# PowerPrototype.net
KiCad netlist of a schematic drawn in EAGLE
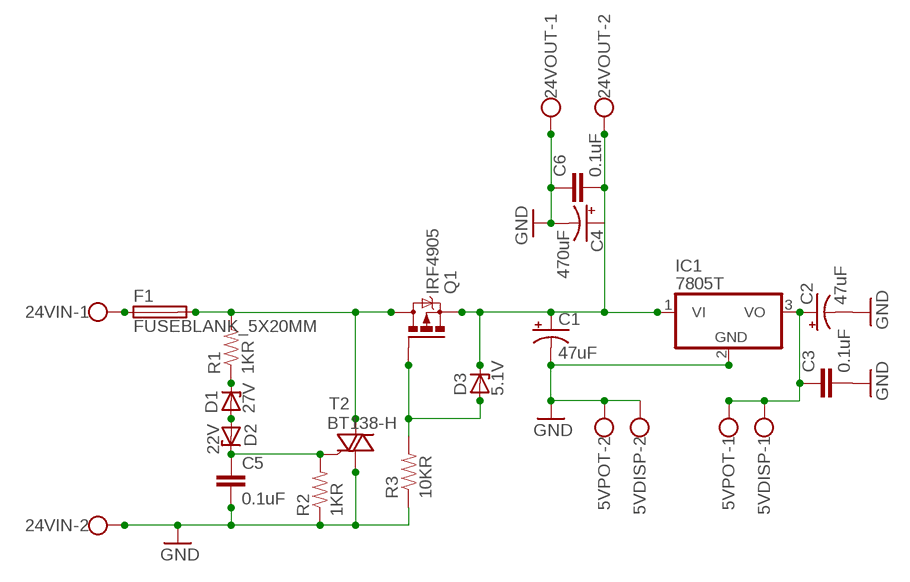
[diagram p0: schematic, sheet 1]

(export (version "E")
  (design (tool "Eeschema 10.0.6"))
  (components
    (comp (ref "5VDISP")
      (value "W237-102")
      (footprint "eagle-import:W237-102")
      (fields (field (name "MPN") "237-102"))
      (libsource (lib "eagle-import") (part "W237-102"))
    )
    (comp (ref "5VPOT")
      (value "W237-102")
      (footprint "eagle-import:W237-102")
      (fields (field (name "MPN") "237-102"))
      (libsource (lib "eagle-import") (part "W237-102"))
    )
    (comp (ref "24VIN")
      (value "W237-102")
      (footprint "eagle-import:W237-102")
      (fields (field (name "MPN") "237-102"))
      (libsource (lib "eagle-import") (part "W237-102"))
    )
    (comp (ref "24VOUT")
      (value "W237-102")
      (footprint "eagle-import:W237-102")
      (fields (field (name "MPN") "237-102"))
      (libsource (lib "eagle-import") (part "W237-102"))
    )
    (comp (ref "C1")
      (value "47uF")
      (footprint "eagle-import:E2,5-5")
      (libsource (lib "eagle-import") (part "CPOL-USE2.5-5"))
    )
    (comp (ref "C2")
      (value "47uF")
      (footprint "eagle-import:E2,5-5")
      (libsource (lib "eagle-import") (part "CPOL-USE2.5-5"))
    )
    (comp (ref "C3")
      (value "0.1uF")
      (footprint "eagle-import:CAP-PTH-5MM")
      (libsource (lib "eagle-import") (part "CAPPTH1"))
    )
    (comp (ref "C4")
      (value "470uF")
      (footprint "eagle-import:E2,5-5")
      (libsource (lib "eagle-import") (part "CPOL-USE2.5-5"))
    )
    (comp (ref "C5")
      (value "0.1uF")
      (footprint "eagle-import:CAP-PTH-5MM")
      (libsource (lib "eagle-import") (part "CAPPTH1"))
    )
    (comp (ref "C6")
      (value "0.1uF")
      (footprint "eagle-import:CAP-PTH-5MM")
      (libsource (lib "eagle-import") (part "CAPPTH1"))
    )
    (comp (ref "D1")
      (value "27V")
      (footprint "eagle-import:ZDIO-5")
      (libsource (lib "eagle-import") (part "ZENER-DIODEZD-5"))
    )
    (comp (ref "D2")
      (value "22V")
      (footprint "eagle-import:ZDIO-5")
      (libsource (lib "eagle-import") (part "ZENER-DIODEZD-5"))
    )
    (comp (ref "D3")
      (value "5.1V")
      (footprint "eagle-import:ZDIO-7.5")
      (libsource (lib "eagle-import") (part "ZENER-DIODEZD-7.5"))
    )
    (comp (ref "F1")
      (value "FUSEBLANK_5X20MM")
      (footprint "eagle-import:FUSE_HOLDER_5X20MM")
      (libsource (lib "eagle-import") (part "FUSEBLANK_5X20MM"))
    )
    (comp (ref "IC1")
      (value "7805T")
      (footprint "eagle-import:TO220H")
      (libsource (lib "eagle-import") (part "78T05"))
    )
    (comp (ref "Q1")
      (value "IRF4905")
      (footprint "eagle-import:TO220BH")
      (libsource (lib "eagle-import") (part "IRF4905"))
    )
    (comp (ref "R1")
      (value "1KR")
      (footprint "eagle-import:AXIAL-0.3")
      (libsource (lib "eagle-import") (part "RESISTORAXIAL-0.3"))
    )
    (comp (ref "R2")
      (value "1KR")
      (footprint "eagle-import:AXIAL-0.3")
      (libsource (lib "eagle-import") (part "RESISTORAXIAL-0.3"))
    )
    (comp (ref "R3")
      (value "10KR")
      (footprint "eagle-import:AXIAL-0.3")
      (libsource (lib "eagle-import") (part "RESISTORAXIAL-0.3"))
    )
    (comp (ref "T2")
      (value "BT138-H")
      (footprint "eagle-import:TO220BH")
      (libsource (lib "eagle-import") (part "BT138-H"))
    )
  )
  (nets
    (net (code "1") (name "GND") (class "Default")
      (node (ref "24VIN") (pin "2") (pinfunction "KL_2") (pintype "passive"))
      (node (ref "24VOUT") (pin "1") (pinfunction "KL_1") (pintype "passive"))
      (node (ref "5VDISP") (pin "2") (pinfunction "KL_2") (pintype "passive"))
      (node (ref "5VPOT") (pin "2") (pinfunction "KL_2") (pintype "passive"))
      (node (ref "C1") (pin "-") (pinfunction "-_-") (pintype "passive"))
      (node (ref "C2") (pin "-") (pinfunction "-_-") (pintype "passive"))
      (node (ref "C3") (pin "2") (pinfunction "2_2") (pintype "passive"))
      (node (ref "C4") (pin "-") (pinfunction "-_-") (pintype "passive"))
      (node (ref "C5") (pin "2") (pinfunction "2_2") (pintype "passive"))
      (node (ref "C6") (pin "1") (pinfunction "1_1") (pintype "passive"))
      (node (ref "IC1") (pin "2") (pinfunction "GND_2") (pintype "passive"))
      (node (ref "R2") (pin "P$1") (pinfunction "1_P$1") (pintype "passive"))
      (node (ref "R3") (pin "P$1") (pinfunction "1_P$1") (pintype "passive"))
      (node (ref "T2") (pin "T1") (pinfunction "A1_T1") (pintype "passive"))
    )
    (net (code "2") (name "Net-(5VDISPA-KL)") (class "Default")
      (node (ref "5VDISP") (pin "1") (pinfunction "KL_1") (pintype "passive"))
      (node (ref "5VPOT") (pin "1") (pinfunction "KL_1") (pintype "passive"))
      (node (ref "C2") (pin "+") (pinfunction "+_+") (pintype "passive"))
      (node (ref "C3") (pin "1") (pinfunction "1_1") (pintype "passive"))
      (node (ref "IC1") (pin "3") (pinfunction "VO_3") (pintype "passive"))
    )
    (net (code "3") (name "Net-(24VINA-KL)") (class "Default")
      (node (ref "24VIN") (pin "1") (pinfunction "KL_1") (pintype "passive"))
      (node (ref "F1") (pin "1") (pinfunction "1_1") (pintype "passive"))
    )
    (net (code "4") (name "Net-(24VOUTB-KL)") (class "Default")
      (node (ref "24VOUT") (pin "2") (pinfunction "KL_2") (pintype "passive"))
      (node (ref "C1") (pin "+") (pinfunction "+_+") (pintype "passive"))
      (node (ref "C4") (pin "+") (pinfunction "+_+") (pintype "passive"))
      (node (ref "C6") (pin "2") (pinfunction "2_2") (pintype "passive"))
      (node (ref "D3") (pin "C") (pinfunction "C_C") (pintype "passive"))
      (node (ref "IC1") (pin "1") (pinfunction "VI_1") (pintype "input"))
      (node (ref "Q1") (pin "S") (pinfunction "S_S") (pintype "passive"))
    )
    (net (code "5") (name "Net-(D1-PadA)") (class "Default")
      (node (ref "D1") (pin "A") (pinfunction "A_A") (pintype "passive"))
      (node (ref "D2") (pin "A") (pinfunction "A_A") (pintype "passive"))
    )
    (net (code "6") (name "Net-(R1-1)") (class "Default")
      (node (ref "D1") (pin "C") (pinfunction "C_C") (pintype "passive"))
      (node (ref "R1") (pin "P$1") (pinfunction "1_P$1") (pintype "passive"))
    )
    (net (code "7") (name "Net-(R1-2)") (class "Default")
      (node (ref "F1") (pin "2") (pinfunction "2_2") (pintype "passive"))
      (node (ref "Q1") (pin "D") (pinfunction "D_D") (pintype "passive"))
      (node (ref "R1") (pin "P$2") (pinfunction "2_P$2") (pintype "passive"))
      (node (ref "T2") (pin "T2") (pinfunction "A2_T2") (pintype "passive"))
    )
    (net (code "8") (name "Net-(R2-2)") (class "Default")
      (node (ref "C5") (pin "1") (pinfunction "1_1") (pintype "passive"))
      (node (ref "D2") (pin "C") (pinfunction "C_C") (pintype "passive"))
      (node (ref "R2") (pin "P$2") (pinfunction "2_P$2") (pintype "passive"))
      (node (ref "T2") (pin "G") (pinfunction "G_G") (pintype "passive"))
    )
    (net (code "9") (name "Net-(R3-2)") (class "Default")
      (node (ref "D3") (pin "A") (pinfunction "A_A") (pintype "passive"))
      (node (ref "Q1") (pin "G") (pinfunction "G_G") (pintype "passive"))
      (node (ref "R3") (pin "P$2") (pinfunction "2_P$2") (pintype "passive"))
    )
  )
)
